# FlipFlop.net
KiCad netlist of a schematic drawn in Altium Designer
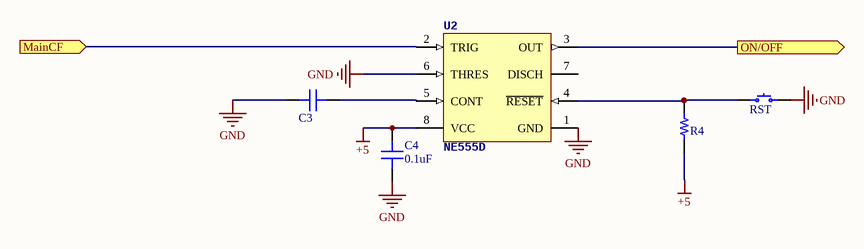
[diagram p0: FlipFlop.SchDoc]

(export (version "E")
  (design (tool "Eeschema 10.0.6"))
  (components
    (comp (ref "C3")
      (value "10000pF")
      (footprint "CAP 0805/2012")
      (description "CAP CER 10000PF 25V X7R 0805")
      (fields
        (field (name "PART NUMBER") "CL21B103KAANNNC")
        (field (name "MANUFACTURER") "Samsung Electro-Mechanics America, Inc.")
      )
      (libsource (lib "Celestial Library Database") (part "Capacitor"))
    )
    (comp (ref "C4")
      (value "0.1uF")
      (footprint "CAP 0805/2012")
      (description "CAP CER 0.1UF 25V X7R 0805")
      (fields
        (field (name "PART NUMBER") "CL21B104KACNNNC")
        (field (name "MANUFACTURER") "Samsung Electro-Mechanics America, Inc.")
      )
      (libsource (lib "Celestial Library Database") (part "Capacitor"))
    )
    (comp (ref "R4")
      (value "10k")
      (footprint "RES 1206/3216")
      (description "RES SMD 10K OHM 1% 1/4W 1206")
      (fields
        (field (name "PART NUMBER") "ERJ-8ENF1002V")
        (field (name "MANUFACTURER") "Panasonic Electronic Components")
      )
      (libsource (lib "Celestial Library Database") (part "Resistor"))
    )
    (comp (ref "RST")
      (value "AB11AH-HC")
      (footprint "NKK AB11AH-HC")
      (description "SWITCH PUSH SPST-NO 0.4VA 28V")
      (fields (field (name "MANUFACTURER") "NKK Switches"))
      (libsource (lib "Celestial Library Database") (part "NKK AB11AH-HA"))
    )
    (comp (ref "U2")
      (value "NE555D")
      (footprint "D0008A_L")
      (description "Precision Timer, 4.5 to 16 V, 0 to 70 degC, 8-Pin SOIC (D), Green (RoHS & no Sb/Br), Tube")
      (fields (field (name "PARTNUMBER") "NE555") (field (name "MANUFACTURER") "Texas Instruments"))
      (libsource (lib "Altium Content Vault") (part "TI-XX555-8"))
    )
  )
  (nets
    (net (code "1") (name "+5") (class "Default")
      (node (ref "C4") (pin "2") (pinfunction "2_2") (pintype "passive"))
      (node (ref "R4") (pin "2") (pinfunction "2_2") (pintype "passive"))
      (node (ref "U2") (pin "8") (pinfunction "VCC_8") (pintype "power_in"))
    )
    (net (code "2") (name "/MainCF") (class "Default")
      (node (ref "U2") (pin "2") (pinfunction "TRIG_2") (pintype "input"))
    )
    (net (code "3") (name "/ON{slash}OFF") (class "Default")
      (node (ref "U2") (pin "3") (pinfunction "OUT_3") (pintype "output"))
    )
    (net (code "4") (name "GND") (class "Default")
      (node (ref "C3") (pin "1") (pinfunction "1_1") (pintype "passive"))
      (node (ref "C4") (pin "1") (pinfunction "1_1") (pintype "passive"))
      (node (ref "RST") (pin "3") (pinfunction "3_3") (pintype "passive"))
      (node (ref "U2") (pin "1") (pinfunction "GND_1") (pintype "power_in"))
      (node (ref "U2") (pin "6") (pinfunction "THRES_6") (pintype "input"))
    )
    (net (code "5") (name "Net-(U2-CONT)") (class "Default")
      (node (ref "C3") (pin "2") (pinfunction "2_2") (pintype "passive"))
      (node (ref "U2") (pin "5") (pinfunction "CONT_5") (pintype "input"))
    )
    (net (code "6") (name "Net-(U2-~{RESET})") (class "Default")
      (node (ref "R4") (pin "1") (pinfunction "1_1") (pintype "passive"))
      (node (ref "RST") (pin "1") (pinfunction "1_1") (pintype "passive"))
      (node (ref "U2") (pin "4") (pinfunction "~{RESET}_4") (pintype "input"))
    )
    (net (code "7") (name "unconnected-(U2-DISCH-Pad7)") (class "Default")
      (node (ref "U2") (pin "7") (pinfunction "DISCH_7") (pintype "open_collector"))
    )
  )
)
